# Net520.net
KiCad netlist of a schematic drawn in Altium Designer
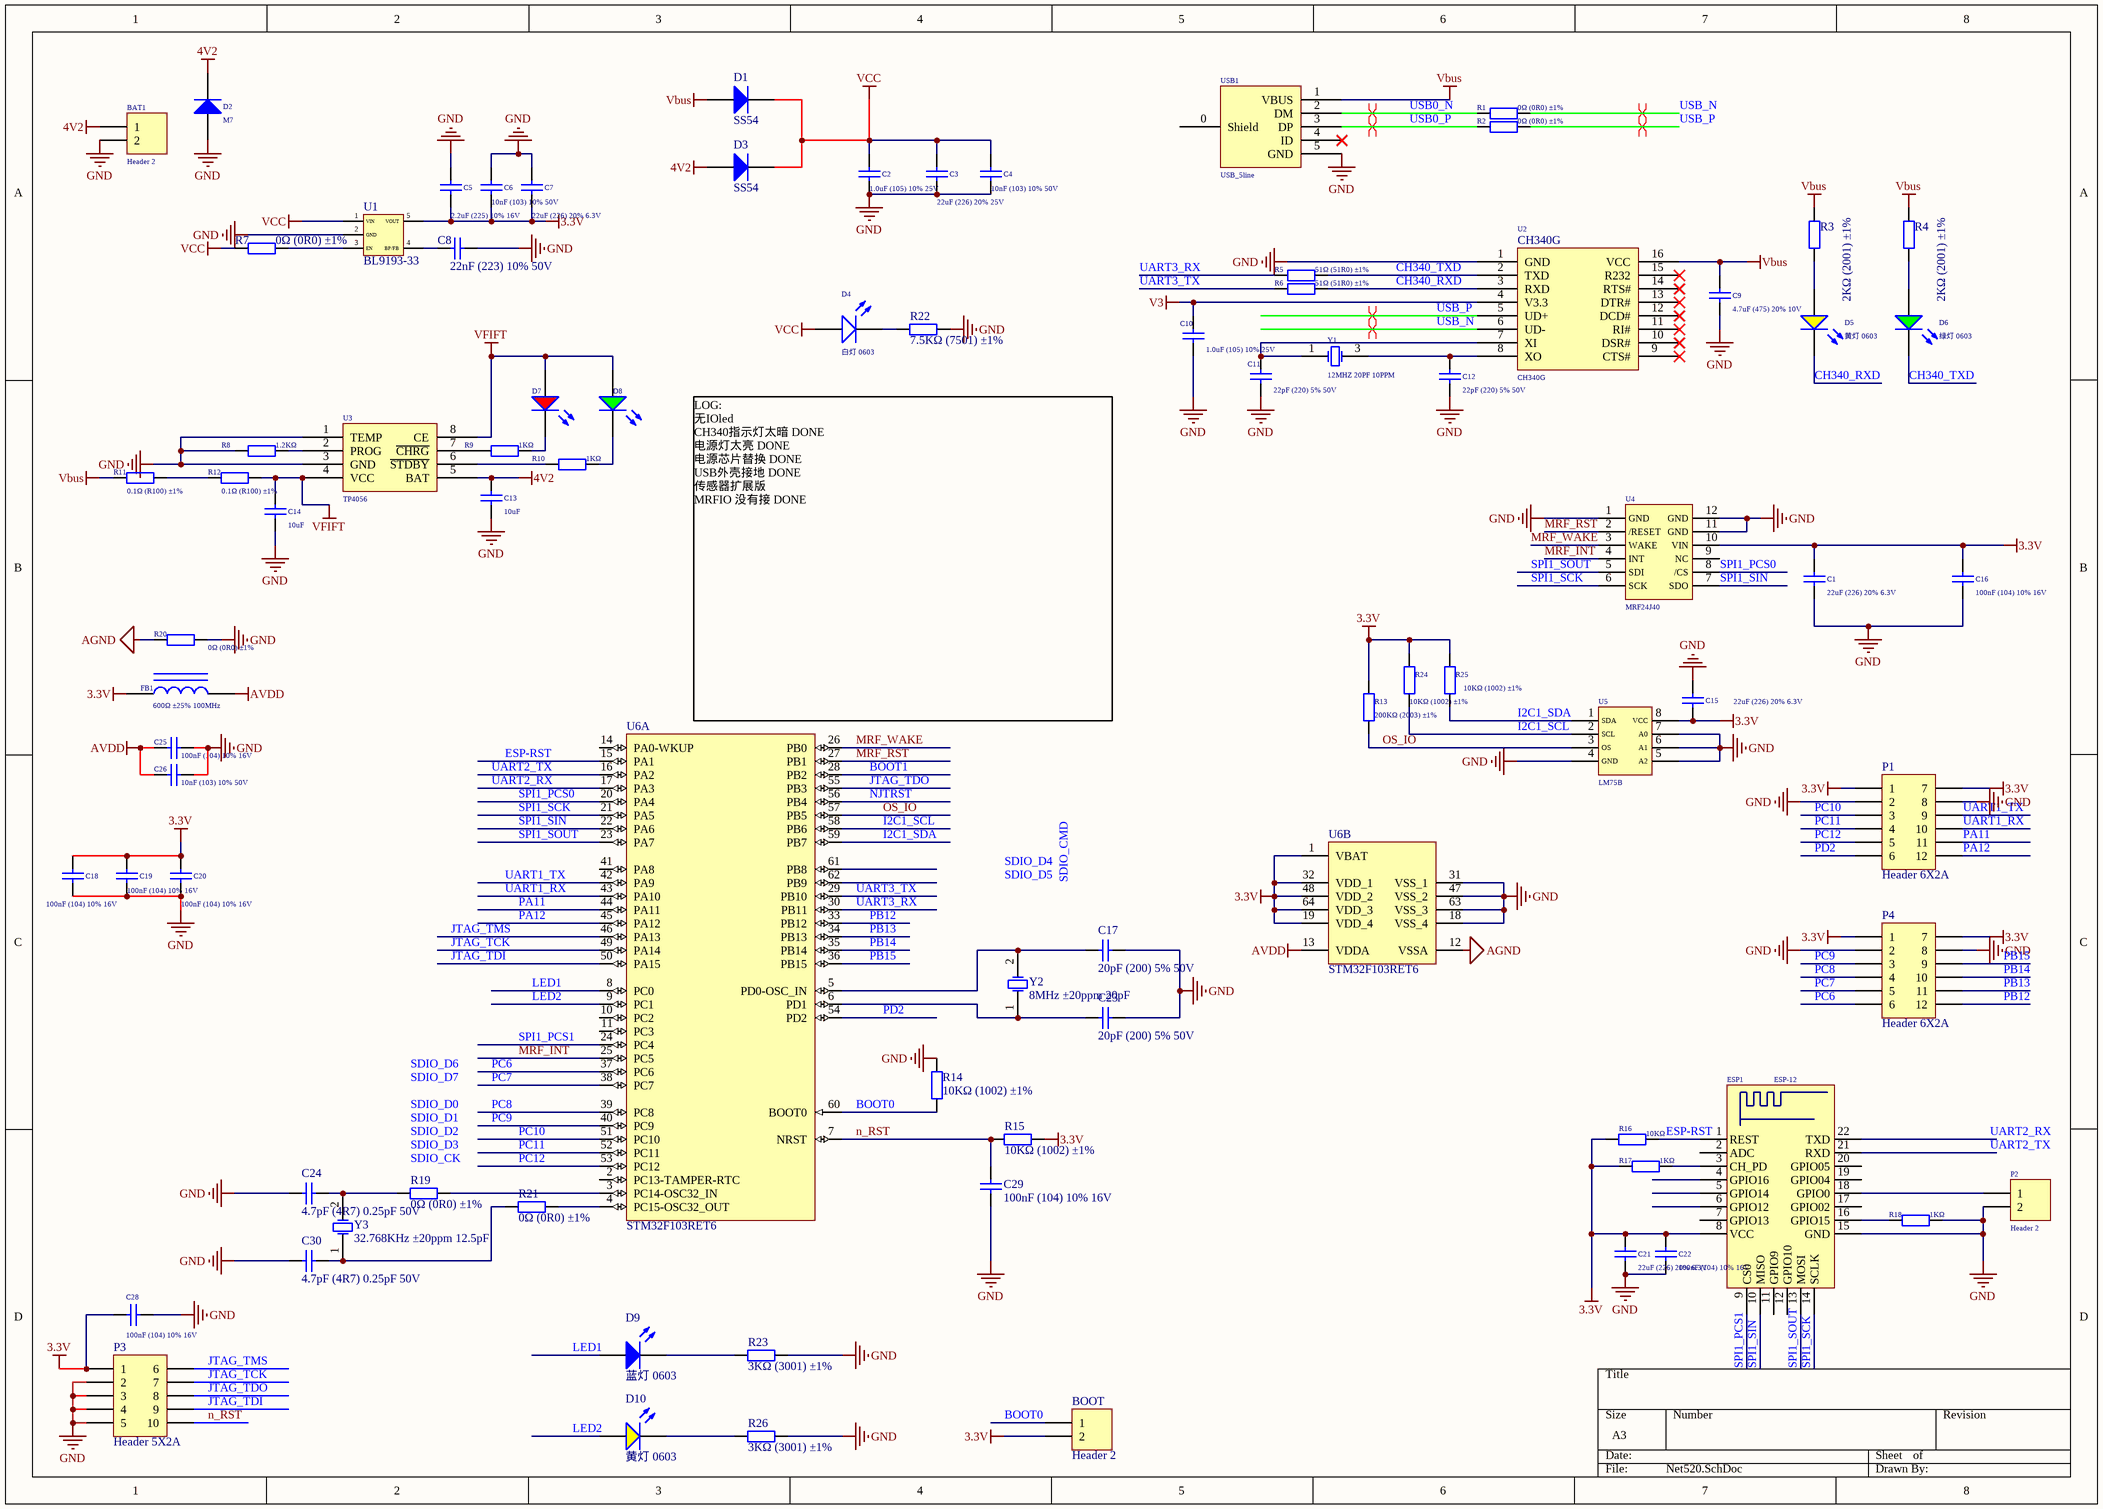
[diagram p0: Net520.SchDoc]

(export (version "E")
  (design (tool "Eeschema 10.0.6"))
  (components
    (comp (ref "BAT1")
      (value "Header 2")
      (footprint "HDR1X2")
      (description "Header, 2-Pin")
      (fields (field (name "PUBLISHER") "Altium Limited"))
      (libsource (lib "Sparks") (part "Header 2"))
    )
    (comp (ref "BOOT")
      (value "Header 2")
      (footprint "HDR1X2")
      (description "Header, 2-Pin")
      (fields (field (name "PUBLISHER") "Altium Limited"))
      (libsource (lib "Sparks") (part "Header 2"))
    )
    (comp (ref "C1")
      (value "22uF (226) 20% 6.3V")
      (footprint "0603_C")
      (description "贴片电容")
      (libsource (lib "Miscellaneous Devices LC") (part "0603 22uF (226) 20% 6.3V"))
    )
    (comp (ref "C2")
      (value "1.0uF (105) 10% 25V")
      (footprint "0402_C")
      (description "贴片电容")
      (libsource (lib "Miscellaneous Devices LC") (part "0402 1.0uF (105) 10% 25V"))
    )
    (comp (ref "C3")
      (value "22uF (226) 20% 25V")
      (footprint "0805_C")
      (description "贴片电容")
      (libsource (lib "Miscellaneous Devices LC") (part "0805 22uF (226) 20% 25V"))
    )
    (comp (ref "C4")
      (value "10nF (103) 10% 50V")
      (footprint "0402_C")
      (description "贴片电容")
      (libsource (lib "Miscellaneous Devices LC") (part "0402 10nF (103) 10% 50V"))
    )
    (comp (ref "C5")
      (value "2.2uF (225) 10% 16V")
      (footprint "0603_C")
      (description "贴片电容")
      (libsource (lib "Miscellaneous Devices LC") (part "0603 2.2uF (225) 10% 16V"))
    )
    (comp (ref "C6")
      (value "10nF (103) 10% 50V")
      (footprint "0402_C")
      (description "贴片电容")
      (libsource (lib "Miscellaneous Devices LC") (part "0402 10nF (103) 10% 50V"))
    )
    (comp (ref "C7")
      (value "22uF (226) 20% 6.3V")
      (footprint "0603_C")
      (description "贴片电容")
      (libsource (lib "Miscellaneous Devices LC") (part "0603 22uF (226) 20% 6.3V"))
    )
    (comp (ref "C8")
      (value "22nF (223) 10% 50V")
      (footprint "0402_C")
      (description "贴片电容")
      (libsource (lib "Miscellaneous Devices LC") (part "0402 22nF (223) 10% 50V"))
    )
    (comp (ref "C9")
      (value "4.7uF (475) 20% 10V")
      (footprint "0402_C")
      (description "贴片电容")
      (libsource (lib "Miscellaneous Devices LC") (part "0402 4.7uF (475) 20% 10V"))
    )
    (comp (ref "C10")
      (value "1.0uF (105) 10% 25V")
      (footprint "0402_C")
      (description "贴片电容")
      (libsource (lib "Miscellaneous Devices LC") (part "0402 1.0uF (105) 10% 25V"))
    )
    (comp (ref "C11")
      (value "22pF (220) 5% 50V")
      (footprint "0402_C")
      (description "贴片电容")
      (libsource (lib "Miscellaneous Devices LC") (part "0402 22pF (220) 5% 50V"))
    )
    (comp (ref "C12")
      (value "22pF (220) 5% 50V")
      (footprint "0402_C")
      (description "贴片电容")
      (libsource (lib "Miscellaneous Devices LC") (part "0402 22pF (220) 5% 50V"))
    )
    (comp (ref "C13")
      (value "10uF")
      (footprint "0402_C")
      (description "贴片电容")
      (libsource (lib "Cap") (part "0402 10uF (106) 20% 6.3V"))
    )
    (comp (ref "C14")
      (value "10uF")
      (footprint "0402_C")
      (description "贴片电容")
      (libsource (lib "Cap") (part "0402 10uF (106) 20% 6.3V"))
    )
    (comp (ref "C15")
      (value "22uF (226) 20% 6.3V")
      (footprint "0603_C")
      (description "贴片电容")
      (libsource (lib "Miscellaneous Devices LC") (part "0603 22uF (226) 20% 6.3V"))
    )
    (comp (ref "C16")
      (value "100nF (104) 10% 16V")
      (footprint "0402_C")
      (description "贴片电容")
      (libsource (lib "Miscellaneous Devices LC") (part "0402 100nF (104) 10% 16V"))
    )
    (comp (ref "C17")
      (value "20pF (200) 5% 50V")
      (footprint "0402_C")
      (description "贴片电容")
      (libsource (lib "Miscellaneous Devices LC") (part "0402 20pF (200) 5% 50V"))
    )
    (comp (ref "C18")
      (value "100nF (104) 10% 16V")
      (footprint "0402_C")
      (description "贴片电容")
      (libsource (lib "Miscellaneous Devices LC") (part "0402 100nF (104) 10% 16V"))
    )
    (comp (ref "C19")
      (value "100nF (104) 10% 16V")
      (footprint "0402_C")
      (description "贴片电容")
      (libsource (lib "Miscellaneous Devices LC") (part "0402 100nF (104) 10% 16V"))
    )
    (comp (ref "C20")
      (value "100nF (104) 10% 16V")
      (footprint "0402_C")
      (description "贴片电容")
      (libsource (lib "Miscellaneous Devices LC") (part "0402 100nF (104) 10% 16V"))
    )
    (comp (ref "C21")
      (value "22uF (226) 20% 6.3V")
      (footprint "0603_C")
      (description "贴片电容")
      (libsource (lib "Miscellaneous Devices LC") (part "0603 22uF (226) 20% 6.3V"))
    )
    (comp (ref "C22")
      (value "100nF (104) 10% 16V")
      (footprint "0402_C")
      (description "贴片电容")
      (libsource (lib "Miscellaneous Devices LC") (part "0402 100nF (104) 10% 16V"))
    )
    (comp (ref "C23")
      (value "20pF (200) 5% 50V")
      (footprint "0402_C")
      (description "贴片电容")
      (libsource (lib "Miscellaneous Devices LC") (part "0402 20pF (200) 5% 50V"))
    )
    (comp (ref "C24")
      (value "4.7pF (4R7) 0.25pF 50V")
      (footprint "0402_C")
      (description "贴片电容")
      (libsource (lib "Miscellaneous Devices LC") (part "0402 4.7pF (4R7) 0.25pF 50V"))
    )
    (comp (ref "C25")
      (value "100nF (104) 10% 16V")
      (footprint "0402_C")
      (description "贴片电容")
      (libsource (lib "Miscellaneous Devices LC") (part "0402 100nF (104) 10% 16V"))
    )
    (comp (ref "C26")
      (value "10nF (103) 10% 50V")
      (footprint "0402_C")
      (description "贴片电容")
      (libsource (lib "Miscellaneous Devices LC") (part "0402 10nF (103) 10% 50V"))
    )
    (comp (ref "C28")
      (value "100nF (104) 10% 16V")
      (footprint "0402_C")
      (description "贴片电容")
      (libsource (lib "Miscellaneous Devices LC") (part "0402 100nF (104) 10% 16V"))
    )
    (comp (ref "C29")
      (value "100nF (104) 10% 16V")
      (footprint "0402_C")
      (description "贴片电容")
      (libsource (lib "Miscellaneous Devices LC") (part "0402 100nF (104) 10% 16V"))
    )
    (comp (ref "C30")
      (value "4.7pF (4R7) 0.25pF 50V")
      (footprint "0402_C")
      (description "贴片电容")
      (libsource (lib "Miscellaneous Devices LC") (part "0402 4.7pF (4R7) 0.25pF 50V"))
    )
    (comp (ref "D1")
      (value "SS54")
      (footprint "SMA(DO-214AC)_S1")
      (description "二极管")
      (libsource (lib "Miscellaneous Devices LC") (part "SMA(DO-214AC) SS54"))
    )
    (comp (ref "D2")
      (value "M7")
      (footprint "SMA(DO-214AC)_S1")
      (description "二极管")
      (libsource (lib "Miscellaneous Devices LC") (part "SMA(DO-214AC) M7"))
    )
    (comp (ref "D3")
      (value "SS54")
      (footprint "SMA(DO-214AC)_S1")
      (description "二极管")
      (libsource (lib "Miscellaneous Devices LC") (part "SMA(DO-214AC) SS54"))
    )
    (comp (ref "D4")
      (value "白灯 0603")
      (footprint "0603_LED_S1")
      (description "发光二极管")
      (libsource (lib "Miscellaneous Devices LC") (part "0603 白灯"))
    )
    (comp (ref "D5")
      (value "黄灯 0603")
      (footprint "0603_LED_S1")
      (description "发光二极管")
      (libsource (lib "Miscellaneous Devices LC") (part "0603 黄灯"))
    )
    (comp (ref "D6")
      (value "绿灯 0603")
      (footprint "0603_LED_S1")
      (description "发光二极管")
      (libsource (lib "Miscellaneous Devices LC") (part "0603 绿灯"))
    )
    (comp (ref "D7")
      (value "红灯 0603")
      (footprint "0603_LED_S1")
      (description "发光二极管")
      (libsource (lib "LED") (part "0603 红灯"))
    )
    (comp (ref "D8")
      (value "绿灯 0603")
      (footprint "0603_LED_S1")
      (description "发光二极管")
      (libsource (lib "LED") (part "0603 绿灯"))
    )
    (comp (ref "D9")
      (value "蓝灯 0603")
      (footprint "0603_LED_S1")
      (description "发光二极管")
      (libsource (lib "Miscellaneous Devices LC") (part "0603 蓝灯"))
    )
    (comp (ref "D10")
      (value "黄灯 0603")
      (footprint "0603_LED_S1")
      (description "发光二极管")
      (libsource (lib "Miscellaneous Devices LC") (part "0603 黄灯"))
    )
    (comp (ref "ESP1") (value "ESP-12") (footprint "ESP-12") (libsource (lib "2号库") (part "ESP-12")))
    (comp (ref "FB1")
      (value "600Ω ±25% 100MHz")
      (footprint "0805_L")
      (description "贴片磁珠")
      (libsource (lib "Miscellaneous Devices LC") (part "0805 600Ω 25% 100MHz"))
    )
    (comp (ref "P1")
      (value "Header 6X2A")
      (footprint "SMT-HEADER 6*2")
      (description "Header, 6-Pin, Dual row")
      (fields (field (name "PUBLISHER") "Altium Limited"))
      (libsource (lib "Miscellaneous Connectors") (part "Header 6X2A"))
    )
    (comp (ref "P2")
      (value "Header 2")
      (footprint "HDR1X2")
      (description "Header, 2-Pin")
      (fields (field (name "PUBLISHER") "Altium Limited"))
      (libsource (lib "Sparks") (part "Header 2"))
    )
    (comp (ref "P3")
      (value "Header 5X2A")
      (footprint "SMT HEADER 5*2")
      (description "Header, 5-Pin, Dual row")
      (fields (field (name "PUBLISHER") "Altium Limited"))
      (libsource (lib "Miscellaneous Connectors") (part "Header 5X2A"))
    )
    (comp (ref "P4")
      (value "Header 6X2A")
      (footprint "SMT-HEADER 6*2")
      (description "Header, 6-Pin, Dual row")
      (fields (field (name "PUBLISHER") "Altium Limited"))
      (libsource (lib "Miscellaneous Connectors") (part "Header 6X2A"))
    )
    (comp (ref "R1")
      (value "0Ω (0R0) ±1%")
      (footprint "0402_R")
      (description "贴片电阻")
      (libsource (lib "Miscellaneous Devices LC") (part "0402 0Ω (0R0) 1%"))
    )
    (comp (ref "R2")
      (value "0Ω (0R0) ±1%")
      (footprint "0402_R")
      (description "贴片电阻")
      (libsource (lib "Miscellaneous Devices LC") (part "0402 0Ω (0R0) 1%"))
    )
    (comp (ref "R3")
      (value "2KΩ (2001) ±1%")
      (footprint "0402_R")
      (description "贴片电阻")
      (libsource (lib "") (part "0402 2KΩ (2001) 1%_1"))
    )
    (comp (ref "R4")
      (value "2KΩ (2001) ±1%")
      (footprint "0402_R")
      (description "贴片电阻")
      (libsource (lib "Miscellaneous Devices LC") (part "0402 2KΩ (2001) 1%"))
    )
    (comp (ref "R5")
      (value "51Ω (51R0) ±1%")
      (footprint "0402_R")
      (description "贴片电阻")
      (libsource (lib "Miscellaneous Devices LC") (part "0402 51Ω (51R0) 1%"))
    )
    (comp (ref "R6")
      (value "51Ω (51R0) ±1%")
      (footprint "0402_R")
      (description "贴片电阻")
      (libsource (lib "Miscellaneous Devices LC") (part "0402 51Ω (51R0) 1%"))
    )
    (comp (ref "R7")
      (value "0Ω (0R0) ±1%")
      (footprint "0402_R")
      (description "贴片电阻")
      (libsource (lib "Miscellaneous Devices LC") (part "0402 0Ω (0R0) 1%"))
    )
    (comp (ref "R8")
      (value "1.2KΩ")
      (footprint "0402_R")
      (description "贴片电阻")
      (libsource (lib "RES") (part "0402 1.2KΩ (1201) 1%"))
    )
    (comp (ref "R9")
      (value "1KΩ")
      (footprint "0402_R")
      (description "贴片电阻")
      (libsource (lib "RES") (part "0402 1KΩ (1001) 1%"))
    )
    (comp (ref "R10")
      (value "1KΩ")
      (footprint "0402_R")
      (description "贴片电阻")
      (libsource (lib "RES") (part "0402 1KΩ (1001) 1%"))
    )
    (comp (ref "R11")
      (value "0.1Ω (R100) ±1%")
      (footprint "1206_R")
      (description "贴片电阻")
      (libsource (lib "Miscellaneous Devices LC") (part "1206 0.1Ω (R100) 1%"))
    )
    (comp (ref "R12")
      (value "0.1Ω (R100) ±1%")
      (footprint "1206_R")
      (description "贴片电阻")
      (libsource (lib "Miscellaneous Devices LC") (part "1206 0.1Ω (R100) 1%"))
    )
    (comp (ref "R13")
      (value "200KΩ (2003) ±1%")
      (footprint "0402_R")
      (description "贴片电阻")
      (libsource (lib "Miscellaneous Devices LC") (part "0402 200KΩ (2003) 1%"))
    )
    (comp (ref "R14")
      (value "10KΩ (1002) ±1%")
      (footprint "0402_R")
      (description "贴片电阻")
      (libsource (lib "Miscellaneous Devices LC") (part "0402 10KΩ (1002) 1%"))
    )
    (comp (ref "R15")
      (value "10KΩ (1002) ±1%")
      (footprint "0402_R")
      (description "贴片电阻")
      (libsource (lib "") (part "0402 10KΩ (1002) 1%_1"))
    )
    (comp (ref "R16")
      (value "10KΩ")
      (footprint "0603_R")
      (description "贴片电阻")
      (libsource (lib "RES") (part "0603 10KΩ (1002) 1%"))
    )
    (comp (ref "R17")
      (value "1KΩ")
      (footprint "0603_R")
      (description "贴片电阻")
      (libsource (lib "RES") (part "0603 1KΩ (1001) 1%"))
    )
    (comp (ref "R18")
      (value "1KΩ")
      (footprint "0603_R")
      (description "贴片电阻")
      (libsource (lib "RES") (part "0603 1KΩ (1001) 1%"))
    )
    (comp (ref "R19")
      (value "0Ω (0R0) ±1%")
      (footprint "0402_R")
      (description "贴片电阻")
      (libsource (lib "Miscellaneous Devices LC") (part "0402 0Ω (0R0) 1%"))
    )
    (comp (ref "R20")
      (value "0Ω (0R0) ±1%")
      (footprint "0402_R")
      (description "贴片电阻")
      (libsource (lib "Miscellaneous Devices LC") (part "0402 0Ω (0R0) 1%"))
    )
    (comp (ref "R21")
      (value "0Ω (0R0) ±1%")
      (footprint "0402_R")
      (description "贴片电阻")
      (libsource (lib "Miscellaneous Devices LC") (part "0402 0Ω (0R0) 1%"))
    )
    (comp (ref "R22")
      (value "7.5KΩ (7501) ±1%")
      (footprint "0402_R")
      (description "贴片电阻")
      (libsource (lib "Miscellaneous Devices LC") (part "0402 7.5KΩ (7501) 1%"))
    )
    (comp (ref "R23")
      (value "3KΩ (3001) ±1%")
      (footprint "0603_R")
      (description "贴片电阻")
      (libsource (lib "Miscellaneous Devices LC") (part "0603 3KΩ (3001) 1%"))
    )
    (comp (ref "R24")
      (value "10KΩ (1002) ±1%")
      (footprint "0402_R")
      (description "贴片电阻")
      (libsource (lib "Miscellaneous Devices LC") (part "0402 10KΩ (1002) 1%"))
    )
    (comp (ref "R25")
      (value "10KΩ (1002) ±1%")
      (footprint "0402_R")
      (description "贴片电阻")
      (libsource (lib "Miscellaneous Devices LC") (part "0402 10KΩ (1002) 1%"))
    )
    (comp (ref "R26")
      (value "3KΩ (3001) ±1%")
      (footprint "0603_R")
      (description "贴片电阻")
      (libsource (lib "Miscellaneous Devices LC") (part "0603 3KΩ (3001) 1%"))
    )
    (comp (ref "U1")
      (value "BL9193-33")
      (footprint "LC-SOT-23-5")
      (libsource (lib "jlcUser") (part "BL9193-33"))
    )
    (comp (ref "U2")
      (value "CH340G")
      (footprint "SOIC-16_150mil")
      (description "USB")
      (libsource (lib "Miscellaneous Devices LC") (part "CH340G_[C14267]"))
    )
    (comp (ref "U3")
      (value "TP4056")
      (footprint "SOP-8_EP_150mil")
      (description "电池电源管理")
      (libsource (lib "IC") (part "TP4056_[C16581]"))
    )
    (comp (ref "U4") (value "MRF24J40") (footprint "MRF24J40") (libsource (lib "2号库") (part "MRF24J40")))
    (comp (ref "U5")
      (value "LM75B")
      (footprint "LC-SOIC-8_150mil")
      (libsource (lib "jlcUser") (part "LM75B"))
    )
    (comp (ref "U6")
      (value "STM32F103RET6")
      (footprint "LQFP-64_10x10x05P")
      (description "ARM")
      (libsource (lib "Miscellaneous Devices LC") (part "STM32F103RET6"))
    )
    (comp (ref "USB1")
      (value "USB_5line")
      (footprint "USB-MICRO-5P-2F")
      (libsource (lib "2号库") (part "USB_5line"))
    )
    (comp (ref "Y1")
      (value "12MHZ 20PF 10PPM")
      (footprint "SMD-3225_4P")
      (description "贴片晶振")
      (libsource (lib "Miscellaneous Devices LC") (part "SMD-3225_4P  12MHZ 20PF 10PPM"))
    )
    (comp (ref "Y2")
      (value "8MHz ±20ppm 20pF")
      (footprint "SMD-5032_2P")
      (description "贴片晶振")
      (libsource (lib "Miscellaneous Devices LC") (part "SMD-5032_2P 8MHz 20ppm 20pF"))
    )
    (comp (ref "Y3")
      (value "32.768KHz ±20ppm 12.5pF")
      (footprint "SMD-3215_2P FC - 135")
      (description "贴片晶振")
      (libsource (lib "Miscellaneous Devices LC") (part "SMD-3215_2P 32.768KHz 20ppm 12.5pF"))
    )
  )
  (nets
    (net (code "1") (name "/BOOT0") (class "Default")
      (node (ref "BOOT") (pin "1") (pinfunction "1_1") (pintype "passive"))
      (node (ref "R14") (pin "1") (pinfunction "1_1") (pintype "passive"))
      (node (ref "U6") (pin "60") (pinfunction "BOOT0_60") (pintype "input"))
    )
    (net (code "2") (name "/BOOT1") (class "Default")
      (node (ref "U6") (pin "28") (pinfunction "PB2_28") (pintype "bidirectional"))
    )
    (net (code "3") (name "/CH340_RXD") (class "Default")
      (node (ref "D5") (pin "K") (pinfunction "K_K") (pintype "passive"))
      (node (ref "R6") (pin "2") (pinfunction "2_2") (pintype "passive"))
      (node (ref "U2") (pin "3") (pinfunction "RXD_3") (pintype "passive"))
    )
    (net (code "4") (name "/CH340_TXD") (class "Default")
      (node (ref "D6") (pin "K") (pinfunction "K_K") (pintype "passive"))
      (node (ref "R5") (pin "2") (pinfunction "2_2") (pintype "passive"))
      (node (ref "U2") (pin "2") (pinfunction "TXD_2") (pintype "passive"))
    )
    (net (code "5") (name "/ESP-RST") (class "Default")
      (node (ref "ESP1") (pin "1") (pinfunction "REST_1") (pintype "passive"))
      (node (ref "R16") (pin "2") (pinfunction "2_2") (pintype "passive"))
      (node (ref "U6") (pin "15") (pinfunction "PA1_15") (pintype "bidirectional"))
    )
    (net (code "6") (name "/I2C1_SCL") (class "Default")
      (node (ref "R24") (pin "1") (pinfunction "1_1") (pintype "passive"))
      (node (ref "U5") (pin "2") (pinfunction "SCL_2") (pintype "passive"))
      (node (ref "U6") (pin "58") (pinfunction "PB6_58") (pintype "bidirectional"))
    )
    (net (code "7") (name "/I2C1_SDA") (class "Default")
      (node (ref "R25") (pin "1") (pinfunction "1_1") (pintype "passive"))
      (node (ref "U5") (pin "1") (pinfunction "SDA_1") (pintype "passive"))
      (node (ref "U6") (pin "59") (pinfunction "PB7_59") (pintype "bidirectional"))
    )
    (net (code "8") (name "/JTAG_TCK") (class "Default")
      (node (ref "P3") (pin "7") (pinfunction "7_7") (pintype "passive"))
      (node (ref "U6") (pin "49") (pinfunction "PA14_49") (pintype "bidirectional"))
    )
    (net (code "9") (name "/JTAG_TDI") (class "Default")
      (node (ref "P3") (pin "9") (pinfunction "9_9") (pintype "passive"))
      (node (ref "U6") (pin "50") (pinfunction "PA15_50") (pintype "bidirectional"))
    )
    (net (code "10") (name "/JTAG_TDO") (class "Default")
      (node (ref "P3") (pin "8") (pinfunction "8_8") (pintype "passive"))
      (node (ref "U6") (pin "55") (pinfunction "PB3_55") (pintype "bidirectional"))
    )
    (net (code "11") (name "/JTAG_TMS") (class "Default")
      (node (ref "P3") (pin "6") (pinfunction "6_6") (pintype "passive"))
      (node (ref "U6") (pin "46") (pinfunction "PA13_46") (pintype "bidirectional"))
    )
    (net (code "12") (name "/LED1") (class "Default")
      (node (ref "D9") (pin "A") (pinfunction "A_A") (pintype "passive"))
      (node (ref "U6") (pin "8") (pinfunction "PC0_8") (pintype "bidirectional"))
    )
    (net (code "13") (name "/LED2") (class "Default")
      (node (ref "D10") (pin "A") (pinfunction "A_A") (pintype "passive"))
      (node (ref "U6") (pin "9") (pinfunction "PC1_9") (pintype "bidirectional"))
    )
    (net (code "14") (name "/MRF_INT") (class "Default")
      (node (ref "U4") (pin "4") (pinfunction "INT_4") (pintype "passive"))
      (node (ref "U6") (pin "25") (pinfunction "PC5_25") (pintype "bidirectional"))
    )
    (net (code "15") (name "/MRF_RST") (class "Default")
      (node (ref "U4") (pin "2") (pinfunction "/RESET_2") (pintype "passive"))
      (node (ref "U6") (pin "27") (pinfunction "PB1_27") (pintype "bidirectional"))
    )
    (net (code "16") (name "/MRF_WAKE") (class "Default")
      (node (ref "U4") (pin "3") (pinfunction "WAKE_3") (pintype "passive"))
      (node (ref "U6") (pin "26") (pinfunction "PB0_26") (pintype "bidirectional"))
    )
    (net (code "17") (name "/NJTRST") (class "Default")
      (node (ref "U6") (pin "56") (pinfunction "PB4_56") (pintype "bidirectional"))
    )
    (net (code "18") (name "/OS_IO") (class "Default")
      (node (ref "R13") (pin "1") (pinfunction "1_1") (pintype "passive"))
      (node (ref "U5") (pin "3") (pinfunction "OS_3") (pintype "passive"))
      (node (ref "U6") (pin "57") (pinfunction "PB5_57") (pintype "bidirectional"))
    )
    (net (code "19") (name "/PA11") (class "Default")
      (node (ref "P1") (pin "11") (pinfunction "11_11") (pintype "passive"))
      (node (ref "U6") (pin "44") (pinfunction "PA11_44") (pintype "bidirectional"))
    )
    (net (code "20") (name "/PA12") (class "Default")
      (node (ref "P1") (pin "12") (pinfunction "12_12") (pintype "passive"))
      (node (ref "U6") (pin "45") (pinfunction "PA12_45") (pintype "bidirectional"))
    )
    (net (code "21") (name "/PB12") (class "Default")
      (node (ref "P4") (pin "12") (pinfunction "12_12") (pintype "passive"))
      (node (ref "U6") (pin "33") (pinfunction "PB12_33") (pintype "bidirectional"))
    )
    (net (code "22") (name "/PB13") (class "Default")
      (node (ref "P4") (pin "11") (pinfunction "11_11") (pintype "passive"))
      (node (ref "U6") (pin "34") (pinfunction "PB13_34") (pintype "bidirectional"))
    )
    (net (code "23") (name "/PB14") (class "Default")
      (node (ref "P4") (pin "10") (pinfunction "10_10") (pintype "passive"))
      (node (ref "U6") (pin "35") (pinfunction "PB14_35") (pintype "bidirectional"))
    )
    (net (code "24") (name "/PB15") (class "Default")
      (node (ref "P4") (pin "9") (pinfunction "9_9") (pintype "passive"))
      (node (ref "U6") (pin "36") (pinfunction "PB15_36") (pintype "bidirectional"))
    )
    (net (code "25") (name "/PC6") (class "Default")
      (node (ref "P4") (pin "6") (pinfunction "6_6") (pintype "passive"))
      (node (ref "U6") (pin "37") (pinfunction "PC6_37") (pintype "bidirectional"))
    )
    (net (code "26") (name "/PC7") (class "Default")
      (node (ref "P4") (pin "5") (pinfunction "5_5") (pintype "passive"))
      (node (ref "U6") (pin "38") (pinfunction "PC7_38") (pintype "bidirectional"))
    )
    (net (code "27") (name "/PC8") (class "Default")
      (node (ref "P4") (pin "4") (pinfunction "4_4") (pintype "passive"))
      (node (ref "U6") (pin "39") (pinfunction "PC8_39") (pintype "bidirectional"))
    )
    (net (code "28") (name "/PC9") (class "Default")
      (node (ref "P4") (pin "3") (pinfunction "3_3") (pintype "passive"))
      (node (ref "U6") (pin "40") (pinfunction "PC9_40") (pintype "bidirectional"))
    )
    (net (code "29") (name "/PC10") (class "Default")
      (node (ref "P1") (pin "3") (pinfunction "3_3") (pintype "passive"))
      (node (ref "U6") (pin "51") (pinfunction "PC10_51") (pintype "bidirectional"))
    )
    (net (code "30") (name "/PC11") (class "Default")
      (node (ref "P1") (pin "4") (pinfunction "4_4") (pintype "passive"))
      (node (ref "U6") (pin "52") (pinfunction "PC11_52") (pintype "bidirectional"))
    )
    (net (code "31") (name "/PC12") (class "Default")
      (node (ref "P1") (pin "5") (pinfunction "5_5") (pintype "passive"))
      (node (ref "U6") (pin "53") (pinfunction "PC12_53") (pintype "bidirectional"))
    )
    (net (code "32") (name "/PD2") (class "Default")
      (node (ref "P1") (pin "6") (pinfunction "6_6") (pintype "passive"))
      (node (ref "U6") (pin "54") (pinfunction "PD2_54") (pintype "bidirectional"))
    )
    (net (code "43") (name "/SPI1_PCS0") (class "Default")
      (node (ref "U4") (pin "8") (pinfunction "/CS_8") (pintype "passive"))
      (node (ref "U6") (pin "20") (pinfunction "PA4_20") (pintype "bidirectional"))
    )
    (net (code "44") (name "/SPI1_PCS1") (class "Default")
      (node (ref "ESP1") (pin "9") (pinfunction "CS0_9") (pintype "passive"))
      (node (ref "U6") (pin "24") (pinfunction "PC4_24") (pintype "bidirectional"))
    )
    (net (code "45") (name "/SPI1_SCK") (class "Default")
      (node (ref "ESP1") (pin "14") (pinfunction "SCLK_14") (pintype "passive"))
      (node (ref "U4") (pin "6") (pinfunction "SCK_6") (pintype "passive"))
      (node (ref "U6") (pin "21") (pinfunction "PA5_21") (pintype "bidirectional"))
    )
    (net (code "46") (name "/SPI1_SIN") (class "Default")
      (node (ref "ESP1") (pin "10") (pinfunction "MISO_10") (pintype "passive"))
      (node (ref "U4") (pin "7") (pinfunction "SDO_7") (pintype "passive"))
      (node (ref "U6") (pin "22") (pinfunction "PA6_22") (pintype "bidirectional"))
    )
    (net (code "47") (name "/SPI1_SOUT") (class "Default")
      (node (ref "ESP1") (pin "13") (pinfunction "MOSI_13") (pintype "passive"))
      (node (ref "U4") (pin "5") (pinfunction "SDI_5") (pintype "passive"))
      (node (ref "U6") (pin "23") (pinfunction "PA7_23") (pintype "bidirectional"))
    )
    (net (code "48") (name "/UART1_RX") (class "Default")
      (node (ref "P1") (pin "10") (pinfunction "10_10") (pintype "passive"))
      (node (ref "U6") (pin "43") (pinfunction "PA10_43") (pintype "bidirectional"))
    )
    (net (code "49") (name "/UART1_TX") (class "Default")
      (node (ref "P1") (pin "9") (pinfunction "9_9") (pintype "passive"))
      (node (ref "U6") (pin "42") (pinfunction "PA9_42") (pintype "bidirectional"))
    )
    (net (code "50") (name "/UART2_RX") (class "Default")
      (node (ref "ESP1") (pin "22") (pinfunction "TXD_22") (pintype "passive"))
      (node (ref "U6") (pin "17") (pinfunction "PA3_17") (pintype "bidirectional"))
    )
    (net (code "51") (name "/UART2_TX") (class "Default")
      (node (ref "ESP1") (pin "21") (pinfunction "RXD_21") (pintype "passive"))
      (node (ref "U6") (pin "16") (pinfunction "PA2_16") (pintype "bidirectional"))
    )
    (net (code "52") (name "/UART3_RX") (class "Default")
      (node (ref "R5") (pin "1") (pinfunction "1_1") (pintype "passive"))
      (node (ref "U6") (pin "30") (pinfunction "PB11_30") (pintype "bidirectional"))
    )
    (net (code "53") (name "/UART3_TX") (class "Default")
      (node (ref "R6") (pin "1") (pinfunction "1_1") (pintype "passive"))
      (node (ref "U6") (pin "29") (pinfunction "PB10_29") (pintype "bidirectional"))
    )
    (net (code "54") (name "/USB0_N") (class "Default")
      (node (ref "R1") (pin "1") (pinfunction "1_1") (pintype "passive"))
      (node (ref "USB1") (pin "2") (pinfunction "DM_2") (pintype "passive"))
    )
    (net (code "55") (name "/USB0_P") (class "Default")
      (node (ref "R2") (pin "1") (pinfunction "1_1") (pintype "passive"))
      (node (ref "USB1") (pin "3") (pinfunction "DP_3") (pintype "passive"))
    )
    (net (code "56") (name "/USB_N") (class "Default")
      (node (ref "R1") (pin "2") (pinfunction "2_2") (pintype "passive"))
      (node (ref "U2") (pin "6") (pinfunction "UD-_6") (pintype "passive"))
    )
    (net (code "57") (name "/USB_P") (class "Default")
      (node (ref "R2") (pin "2") (pinfunction "2_2") (pintype "passive"))
      (node (ref "U2") (pin "5") (pinfunction "UD+_5") (pintype "passive"))
    )
    (net (code "58") (name "/n_RST") (class "Default")
      (node (ref "C29") (pin "2") (pinfunction "2_2") (pintype "passive"))
      (node (ref "P3") (pin "10") (pinfunction "10_10") (pintype "passive"))
      (node (ref "R15") (pin "2") (pinfunction "2_2") (pintype "passive"))
      (node (ref "U6") (pin "7") (pinfunction "NRST_7") (pintype "bidirectional"))
    )
    (net (code "59") (name "3.3V") (class "Default")
      (node (ref "BOOT") (pin "2") (pinfunction "2_2") (pintype "passive"))
      (node (ref "C1") (pin "2") (pinfunction "2_2") (pintype "passive"))
      (node (ref "C15") (pin "1") (pinfunction "1_1") (pintype "passive"))
      (node (ref "C16") (pin "2") (pinfunction "2_2") (pintype "passive"))
      (node (ref "C18") (pin "2") (pinfunction "2_2") (pintype "passive"))
      (node (ref "C19") (pin "2") (pinfunction "2_2") (pintype "passive"))
      (node (ref "C20") (pin "2") (pinfunction "2_2") (pintype "passive"))
      (node (ref "C21") (pin "2") (pinfunction "2_2") (pintype "passive"))
      (node (ref "C22") (pin "2") (pinfunction "2_2") (pintype "passive"))
      (node (ref "C28") (pin "1") (pinfunction "1_1") (pintype "passive"))
      (node (ref "C5") (pin "1") (pinfunction "1_1") (pintype "passive"))
      (node (ref "C6") (pin "1") (pinfunction "1_1") (pintype "passive"))
      (node (ref "C7") (pin "1") (pinfunction "1_1") (pintype "passive"))
      (node (ref "ESP1") (pin "8") (pinfunction "VCC_8") (pintype "passive"))
      (node (ref "FB1") (pin "1") (pinfunction "1_1") (pintype "passive"))
      (node (ref "P1") (pin "1") (pinfunction "1_1") (pintype "passive"))
      (node (ref "P1") (pin "7") (pinfunction "7_7") (pintype "passive"))
      (node (ref "P3") (pin "1") (pinfunction "1_1") (pintype "passive"))
      (node (ref "P4") (pin "1") (pinfunction "1_1") (pintype "passive"))
      (node (ref "P4") (pin "7") (pinfunction "7_7") (pintype "passive"))
      (node (ref "R13") (pin "2") (pinfunction "2_2") (pintype "passive"))
      (node (ref "R15") (pin "1") (pinfunction "1_1") (pintype "passive"))
      (node (ref "R16") (pin "1") (pinfunction "1_1") (pintype "passive"))
      (node (ref "R17") (pin "1") (pinfunction "1_1") (pintype "passive"))
      (node (ref "R24") (pin "2") (pinfunction "2_2") (pintype "passive"))
      (node (ref "R25") (pin "2") (pinfunction "2_2") (pintype "passive"))
      (node (ref "U1") (pin "5") (pinfunction "VOUT_5") (pintype "passive"))
      (node (ref "U4") (pin "10") (pinfunction "VIN_10") (pintype "passive"))
      (node (ref "U5") (pin "8") (pinfunction "VCC_8") (pintype "passive"))
      (node (ref "U6") (pin "1") (pinfunction "VBAT_1") (pintype "power_in"))
      (node (ref "U6") (pin "19") (pinfunction "VDD_4_19") (pintype "power_in"))
      (node (ref "U6") (pin "32") (pinfunction "VDD_1_32") (pintype "power_in"))
      (node (ref "U6") (pin "48") (pinfunction "VDD_2_48") (pintype "power_in"))
      (node (ref "U6") (pin "64") (pinfunction "VDD_3_64") (pintype "power_in"))
    )
    (net (code "60") (name "4V2") (class "Default")
      (node (ref "BAT1") (pin "1") (pinfunction "1_1") (pintype "passive"))
      (node (ref "C13") (pin "2") (pinfunction "2_2") (pintype "passive"))
      (node (ref "D2") (pin "2") (pinfunction "K_2") (pintype "passive"))
      (node (ref "D3") (pin "1") (pinfunction "A_1") (pintype "passive"))
      (node (ref "U3") (pin "5") (pinfunction "BAT_5") (pintype "passive"))
    )
    (net (code "61") (name "AGND") (class "Default")
      (node (ref "R20") (pin "1") (pinfunction "1_1") (pintype "passive"))
      (node (ref "U6") (pin "12") (pinfunction "VSSA_12") (pintype "power_in"))
    )
    (net (code "62") (name "AVDD") (class "Default")
      (node (ref "C25") (pin "1") (pinfunction "1_1") (pintype "passive"))
      (node (ref "C26") (pin "1") (pinfunction "1_1") (pintype "passive"))
      (node (ref "FB1") (pin "2") (pinfunction "2_2") (pintype "passive"))
      (node (ref "U6") (pin "13") (pinfunction "VDDA_13") (pintype "power_in"))
    )
    (net (code "63") (name "GND") (class "Default")
      (node (ref "BAT1") (pin "2") (pinfunction "2_2") (pintype "passive"))
      (node (ref "C1") (pin "1") (pinfunction "1_1") (pintype "passive"))
      (node (ref "C10") (pin "1") (pinfunction "1_1") (pintype "passive"))
      (node (ref "C11") (pin "1") (pinfunction "1_1") (pintype "passive"))
      (node (ref "C12") (pin "1") (pinfunction "1_1") (pintype "passive"))
      (node (ref "C13") (pin "1") (pinfunction "1_1") (pintype "passive"))
      (node (ref "C14") (pin "1") (pinfunction "1_1") (pintype "passive"))
      (node (ref "C15") (pin "2") (pinfunction "2_2") (pintype "passive"))
      (node (ref "C16") (pin "1") (pinfunction "1_1") (pintype "passive"))
      (node (ref "C17") (pin "1") (pinfunction "1_1") (pintype "passive"))
      (node (ref "C18") (pin "1") (pinfunction "1_1") (pintype "passive"))
      (node (ref "C19") (pin "1") (pinfunction "1_1") (pintype "passive"))
      (node (ref "C2") (pin "1") (pinfunction "1_1") (pintype "passive"))
      (node (ref "C20") (pin "1") (pinfunction "1_1") (pintype "passive"))
      (node (ref "C21") (pin "1") (pinfunction "1_1") (pintype "passive"))
      (node (ref "C22") (pin "1") (pinfunction "1_1") (pintype "passive"))
      (node (ref "C23") (pin "1") (pinfunction "1_1") (pintype "passive"))
      (node (ref "C24") (pin "1") (pinfunction "1_1") (pintype "passive"))
      (node (ref "C25") (pin "2") (pinfunction "2_2") (pintype "passive"))
      (node (ref "C26") (pin "2") (pinfunction "2_2") (pintype "passive"))
      (node (ref "C28") (pin "2") (pinfunction "2_2") (pintype "passive"))
      (node (ref "C29") (pin "1") (pinfunction "1_1") (pintype "passive"))
      (node (ref "C3") (pin "1") (pinfunction "1_1") (pintype "passive"))
      (node (ref "C30") (pin "1") (pinfunction "1_1") (pintype "passive"))
      (node (ref "C4") (pin "1") (pinfunction "1_1") (pintype "passive"))
      (node (ref "C5") (pin "2") (pinfunction "2_2") (pintype "passive"))
      (node (ref "C6") (pin "2") (pinfunction "2_2") (pintype "passive"))
      (node (ref "C7") (pin "2") (pinfunction "2_2") (pintype "passive"))
      (node (ref "C8") (pin "2") (pinfunction "2_2") (pintype "passive"))
      (node (ref "C9") (pin "1") (pinfunction "1_1") (pintype "passive"))
      (node (ref "D2") (pin "1") (pinfunction "A_1") (pintype "passive"))
      (node (ref "ESP1") (pin "15") (pinfunction "GND_15") (pintype "passive"))
      (node (ref "P1") (pin "2") (pinfunction "2_2") (pintype "passive"))
      (node (ref "P1") (pin "8") (pinfunction "8_8") (pintype "passive"))
      (node (ref "P2") (pin "2") (pinfunction "2_2") (pintype "passive"))
      (node (ref "P3") (pin "2") (pinfunction "2_2") (pintype "passive"))
      (node (ref "P3") (pin "3") (pinfunction "3_3") (pintype "passive"))
      (node (ref "P3") (pin "4") (pinfunction "4_4") (pintype "passive"))
      (node (ref "P3") (pin "5") (pinfunction "5_5") (pintype "passive"))
      (node (ref "P4") (pin "2") (pinfunction "2_2") (pintype "passive"))
      (node (ref "P4") (pin "8") (pinfunction "8_8") (pintype "passive"))
      (node (ref "R14") (pin "2") (pinfunction "2_2") (pintype "passive"))
      (node (ref "R18") (pin "2") (pinfunction "2_2") (pintype "passive"))
      (node (ref "R20") (pin "2") (pinfunction "2_2") (pintype "passive"))
      (node (ref "R22") (pin "2") (pinfunction "2_2") (pintype "passive"))
      (node (ref "R23") (pin "2") (pinfunction "2_2") (pintype "passive"))
      (node (ref "R26") (pin "2") (pinfunction "2_2") (pintype "passive"))
      (node (ref "R8") (pin "1") (pinfunction "1_1") (pintype "passive"))
      (node (ref "U1") (pin "2") (pinfunction "GND_2") (pintype "passive"))
      (node (ref "U2") (pin "1") (pinfunction "GND_1") (pintype "passive"))
      (node (ref "U3") (pin "1") (pinfunction "TEMP_1") (pintype "passive"))
      (node (ref "U3") (pin "3") (pinfunction "GND_3") (pintype "passive"))
      (node (ref "U4") (pin "1") (pinfunction "GND_1") (pintype "passive"))
      (node (ref "U4") (pin "11") (pinfunction "GND_11") (pintype "passive"))
      (node (ref "U4") (pin "12") (pinfunction "GND_12") (pintype "passive"))
      (node (ref "U5") (pin "4") (pinfunction "GND_4") (pintype "passive"))
      (node (ref "U5") (pin "5") (pinfunction "A2_5") (pintype "passive"))
      (node (ref "U5") (pin "6") (pinfunction "A1_6") (pintype "passive"))
      (node (ref "U5") (pin "7") (pinfunction "A0_7") (pintype "passive"))
      (node (ref "U6") (pin "18") (pinfunction "VSS_4_18") (pintype "power_in"))
      (node (ref "U6") (pin "31") (pinfunction "VSS_1_31") (pintype "power_in"))
      (node (ref "U6") (pin "47") (pinfunction "VSS_2_47") (pintype "power_in"))
      (node (ref "U6") (pin "63") (pinfunction "VSS_3_63") (pintype "power_in"))
      (node (ref "USB1") (pin "5") (pinfunction "GND_5") (pintype "passive"))
    )
    (net (code "64") (name "Net-(D4-PadK)") (class "Default")
      (node (ref "D4") (pin "K") (pinfunction "K_K") (pintype "passive"))
      (node (ref "R22") (pin "1") (pinfunction "1_1") (pintype "passive"))
    )
    (net (code "65") (name "Net-(D5-PadA)") (class "Default")
      (node (ref "D5") (pin "A") (pinfunction "A_A") (pintype "passive"))
      (node (ref "R3") (pin "1") (pinfunction "1_1") (pintype "passive"))
    )
    (net (code "66") (name "Net-(D6-PadA)") (class "Default")
      (node (ref "D6") (pin "A") (pinfunction "A_A") (pintype "passive"))
      (node (ref "R4") (pin "2") (pinfunction "2_2") (pintype "passive"))
    )
    (net (code "67") (name "Net-(D7-PadK)") (class "Default")
      (node (ref "D7") (pin "K") (pinfunction "K_K") (pintype "passive"))
      (node (ref "R9") (pin "2") (pinfunction "2_2") (pintype "passive"))
    )
    (net (code "68") (name "Net-(D8-PadK)") (class "Default")
      (node (ref "D8") (pin "K") (pinfunction "K_K") (pintype "passive"))
      (node (ref "R10") (pin "2") (pinfunction "2_2") (pintype "passive"))
    )
    (net (code "69") (name "Net-(D9-PadK)") (class "Default")
      (node (ref "D9") (pin "K") (pinfunction "K_K") (pintype "passive"))
      (node (ref "R23") (pin "1") (pinfunction "1_1") (pintype "passive"))
    )
    (net (code "70") (name "Net-(D10-PadK)") (class "Default")
      (node (ref "D10") (pin "K") (pinfunction "K_K") (pintype "passive"))
      (node (ref "R26") (pin "1") (pinfunction "1_1") (pintype "passive"))
    )
    (net (code "71") (name "Net-(ESP1-CH_PD)") (class "Default")
      (node (ref "ESP1") (pin "3") (pinfunction "CH_PD_3") (pintype "passive"))
      (node (ref "R17") (pin "2") (pinfunction "2_2") (pintype "passive"))
    )
    (net (code "72") (name "Net-(ESP1-GPIO0)") (class "Default")
      (node (ref "ESP1") (pin "18") (pinfunction "GPIO0_18") (pintype "passive"))
      (node (ref "P2") (pin "1") (pinfunction "1_1") (pintype "passive"))
    )
    (net (code "73") (name "Net-(ESP1-GPIO15)") (class "Default")
      (node (ref "ESP1") (pin "16") (pinfunction "GPIO15_16") (pintype "passive"))
      (node (ref "R18") (pin "1") (pinfunction "1_1") (pintype "passive"))
    )
    (net (code "74") (name "Net-(R11-Pad2)") (class "Default")
      (node (ref "R11") (pin "2") (pinfunction "2_2") (pintype "passive"))
      (node (ref "R12") (pin "1") (pinfunction "1_1") (pintype "passive"))
    )
    (net (code "75") (name "Net-(U1-BP{slash}FB)") (class "Default")
      (node (ref "C8") (pin "1") (pinfunction "1_1") (pintype "passive"))
      (node (ref "U1") (pin "4") (pinfunction "BP/FB_4") (pintype "passive"))
    )
    (net (code "76") (name "Net-(U1-EN)") (class "Default")
      (node (ref "R7") (pin "2") (pinfunction "2_2") (pintype "passive"))
      (node (ref "U1") (pin "3") (pinfunction "EN_3") (pintype "passive"))
    )
    (net (code "77") (name "Net-(U2-XI)") (class "Default")
      (node (ref "C11") (pin "2") (pinfunction "2_2") (pintype "passive"))
      (node (ref "U2") (pin "7") (pinfunction "XI_7") (pintype "passive"))
      (node (ref "Y1") (pin "1") (pinfunction "OSC1_1") (pintype "passive"))
    )
    (net (code "78") (name "Net-(U2-XO)") (class "Default")
      (node (ref "C12") (pin "2") (pinfunction "2_2") (pintype "passive"))
      (node (ref "U2") (pin "8") (pinfunction "XO_8") (pintype "passive"))
      (node (ref "Y1") (pin "3") (pinfunction "OSC2_3") (pintype "passive"))
    )
    (net (code "79") (name "Net-(U3-PROG)") (class "Default")
      (node (ref "R8") (pin "2") (pinfunction "2_2") (pintype "passive"))
      (node (ref "U3") (pin "2") (pinfunction "PROG_2") (pintype "passive"))
    )
    (net (code "80") (name "Net-(U3-~{CHRG})") (class "Default")
      (node (ref "R9") (pin "1") (pinfunction "1_1") (pintype "passive"))
      (node (ref "U3") (pin "7") (pinfunction "~{CHRG}_7") (pintype "passive"))
    )
    (net (code "81") (name "Net-(U3-~{STDBY})") (class "Default")
      (node (ref "R10") (pin "1") (pinfunction "1_1") (pintype "passive"))
      (node (ref "U3") (pin "6") (pinfunction "~{STDBY}_6") (pintype "passive"))
    )
    (net (code "82") (name "Net-(U6A-PC14-OSC32_IN)") (class "Default")
      (node (ref "R19") (pin "2") (pinfunction "2_2") (pintype "passive"))
      (node (ref "U6") (pin "3") (pinfunction "PC14-OSC32_IN_3") (pintype "bidirectional"))
    )
    (net (code "83") (name "Net-(U6A-PC15-OSC32_OUT)") (class "Default")
      (node (ref "R21") (pin "2") (pinfunction "2_2") (pintype "passive"))
      (node (ref "U6") (pin "4") (pinfunction "PC15-OSC32_OUT_4") (pintype "bidirectional"))
    )
    (net (code "84") (name "Net-(U6A-PD0-OSC_IN)") (class "Default")
      (node (ref "C17") (pin "2") (pinfunction "2_2") (pintype "passive"))
      (node (ref "U6") (pin "5") (pinfunction "PD0-OSC_IN_5") (pintype "bidirectional"))
      (node (ref "Y2") (pin "2") (pinfunction "OSC2_2") (pintype "passive"))
    )
    (net (code "85") (name "Net-(U6A-PD1)") (class "Default")
      (node (ref "C23") (pin "2") (pinfunction "2_2") (pintype "passive"))
      (node (ref "U6") (pin "6") (pinfunction "PD1_6") (pintype "bidirectional"))
      (node (ref "Y2") (pin "1") (pinfunction "OSC1_1") (pintype "passive"))
    )
    (net (code "86") (name "Net-(Y3-OSC1)") (class "Default")
      (node (ref "C30") (pin "2") (pinfunction "2_2") (pintype "passive"))
      (node (ref "R21") (pin "1") (pinfunction "1_1") (pintype "passive"))
      (node (ref "Y3") (pin "1") (pinfunction "OSC1_1") (pintype "passive"))
    )
    (net (code "87") (name "Net-(Y3-OSC2)") (class "Default")
      (node (ref "C24") (pin "2") (pinfunction "2_2") (pintype "passive"))
      (node (ref "R19") (pin "1") (pinfunction "1_1") (pintype "passive"))
      (node (ref "Y3") (pin "2") (pinfunction "OSC2_2") (pintype "passive"))
    )
    (net (code "88") (name "V3") (class "Default")
      (node (ref "C10") (pin "2") (pinfunction "2_2") (pintype "passive"))
      (node (ref "U2") (pin "4") (pinfunction "V3.3_4") (pintype "passive"))
    )
    (net (code "89") (name "VCC") (class "Default")
      (node (ref "C2") (pin "2") (pinfunction "2_2") (pintype "passive"))
      (node (ref "C3") (pin "2") (pinfunction "2_2") (pintype "passive"))
      (node (ref "C4") (pin "2") (pinfunction "2_2") (pintype "passive"))
      (node (ref "D1") (pin "2") (pinfunction "K_2") (pintype "passive"))
      (node (ref "D3") (pin "2") (pinfunction "K_2") (pintype "passive"))
      (node (ref "D4") (pin "A") (pinfunction "A_A") (pintype "passive"))
      (node (ref "R7") (pin "1") (pinfunction "1_1") (pintype "passive"))
      (node (ref "U1") (pin "1") (pinfunction "VIN_1") (pintype "passive"))
    )
    (net (code "90") (name "VFIFT") (class "Default")
      (node (ref "C14") (pin "2") (pinfunction "2_2") (pintype "passive"))
      (node (ref "D7") (pin "A") (pinfunction "A_A") (pintype "passive"))
      (node (ref "D8") (pin "A") (pinfunction "A_A") (pintype "passive"))
      (node (ref "R12") (pin "2") (pinfunction "2_2") (pintype "passive"))
      (node (ref "U3") (pin "4") (pinfunction "VCC_4") (pintype "passive"))
      (node (ref "U3") (pin "8") (pinfunction "CE_8") (pintype "passive"))
    )
    (net (code "91") (name "Vbus") (class "Default")
      (node (ref "C9") (pin "2") (pinfunction "2_2") (pintype "passive"))
      (node (ref "D1") (pin "1") (pinfunction "A_1") (pintype "passive"))
      (node (ref "R11") (pin "1") (pinfunction "1_1") (pintype "passive"))
      (node (ref "R3") (pin "2") (pinfunction "2_2") (pintype "passive"))
      (node (ref "R4") (pin "1") (pinfunction "1_1") (pintype "passive"))
      (node (ref "U2") (pin "16") (pinfunction "VCC_16") (pintype "passive"))
      (node (ref "USB1") (pin "1") (pinfunction "VBUS_1") (pintype "passive"))
    )
    (net (code "92") (name "unconnected-(ESP1-ADC-Pad2)") (class "Default")
      (node (ref "ESP1") (pin "2") (pinfunction "ADC_2") (pintype "passive"))
    )
    (net (code "93") (name "unconnected-(ESP1-GPIO02-Pad17)") (class "Default")
      (node (ref "ESP1") (pin "17") (pinfunction "GPIO02_17") (pintype "passive"))
    )
    (net (code "94") (name "unconnected-(ESP1-GPIO04-Pad19)") (class "Default")
      (node (ref "ESP1") (pin "19") (pinfunction "GPIO04_19") (pintype "passive"))
    )
    (net (code "95") (name "unconnected-(ESP1-GPIO05-Pad20)") (class "Default")
      (node (ref "ESP1") (pin "20") (pinfunction "GPIO05_20") (pintype "passive"))
    )
    (net (code "96") (name "unconnected-(ESP1-GPIO9-Pad11)") (class "Default")
      (node (ref "ESP1") (pin "11") (pinfunction "GPIO9_11") (pintype "passive"))
    )
    (net (code "97") (name "unconnected-(ESP1-GPIO10-Pad12)") (class "Default")
      (node (ref "ESP1") (pin "12") (pinfunction "GPIO10_12") (pintype "passive"))
    )
    (net (code "98") (name "unconnected-(ESP1-GPIO12-Pad6)") (class "Default")
      (node (ref "ESP1") (pin "6") (pinfunction "GPIO12_6") (pintype "passive"))
    )
    (net (code "99") (name "unconnected-(ESP1-GPIO13-Pad7)") (class "Default")
      (node (ref "ESP1") (pin "7") (pinfunction "GPIO13_7") (pintype "passive"))
    )
    (net (code "100") (name "unconnected-(ESP1-GPIO14-Pad5)") (class "Default")
      (node (ref "ESP1") (pin "5") (pinfunction "GPIO14_5") (pintype "passive"))
    )
    (net (code "101") (name "unconnected-(ESP1-GPIO16-Pad4)") (class "Default")
      (node (ref "ESP1") (pin "4") (pinfunction "GPIO16_4") (pintype "passive"))
    )
    (net (code "102") (name "unconnected-(U2-CTS#-Pad9)") (class "Default")
      (node (ref "U2") (pin "9") (pinfunction "CTS#_9") (pintype "passive+no_connect"))
    )
    (net (code "103") (name "unconnected-(U2-DCD#-Pad12)") (class "Default")
      (node (ref "U2") (pin "12") (pinfunction "DCD#_12") (pintype "passive+no_connect"))
    )
    (net (code "104") (name "unconnected-(U2-DSR#-Pad10)") (class "Default")
      (node (ref "U2") (pin "10") (pinfunction "DSR#_10") (pintype "passive+no_connect"))
    )
    (net (code "105") (name "unconnected-(U2-DTR#-Pad13)") (class "Default")
      (node (ref "U2") (pin "13") (pinfunction "DTR#_13") (pintype "passive+no_connect"))
    )
    (net (code "106") (name "unconnected-(U2-R232-Pad15)") (class "Default")
      (node (ref "U2") (pin "15") (pinfunction "R232_15") (pintype "passive+no_connect"))
    )
    (net (code "107") (name "unconnected-(U2-RI#-Pad11)") (class "Default")
      (node (ref "U2") (pin "11") (pinfunction "RI#_11") (pintype "passive+no_connect"))
    )
    (net (code "108") (name "unconnected-(U2-RTS#-Pad14)") (class "Default")
      (node (ref "U2") (pin "14") (pinfunction "RTS#_14") (pintype "passive+no_connect"))
    )
    (net (code "109") (name "unconnected-(U4-NC-Pad9)") (class "Default")
      (node (ref "U4") (pin "9") (pinfunction "NC_9") (pintype "passive"))
    )
    (net (code "110") (name "unconnected-(U6A-PA0-WKUP-Pad14)") (class "Default")
      (node (ref "U6") (pin "14") (pinfunction "PA0-WKUP_14") (pintype "bidirectional"))
    )
    (net (code "111") (name "unconnected-(U6A-PA8-Pad41)") (class "Default")
      (node (ref "U6") (pin "41") (pinfunction "PA8_41") (pintype "bidirectional"))
    )
    (net (code "112") (name "unconnected-(U6A-PB8-Pad61)") (class "Default")
      (node (ref "U6") (pin "61") (pinfunction "PB8_61") (pintype "bidirectional"))
    )
    (net (code "113") (name "unconnected-(U6A-PB9-Pad62)") (class "Default")
      (node (ref "U6") (pin "62") (pinfunction "PB9_62") (pintype "bidirectional"))
    )
    (net (code "114") (name "unconnected-(U6A-PC2-Pad10)") (class "Default")
      (node (ref "U6") (pin "10") (pinfunction "PC2_10") (pintype "bidirectional"))
    )
    (net (code "115") (name "unconnected-(U6A-PC3-Pad11)") (class "Default")
      (node (ref "U6") (pin "11") (pinfunction "PC3_11") (pintype "bidirectional"))
    )
    (net (code "116") (name "unconnected-(U6A-PC13-TAMPER-RTC-Pad2)") (class "Default")
      (node (ref "U6") (pin "2") (pinfunction "PC13-TAMPER-RTC_2") (pintype "bidirectional"))
    )
    (net (code "117") (name "unconnected-(USB1-ID-Pad4)") (class "Default")
      (node (ref "USB1") (pin "4") (pinfunction "ID_4") (pintype "passive+no_connect"))
    )
    (net (code "118") (name "unconnected-(USB1-Shield-Pad0)") (class "Default")
      (node (ref "USB1") (pin "0") (pinfunction "Shield_0") (pintype "passive"))
    )
  )
)
